# Processor.net
KiCad netlist of a schematic drawn in Altium Designer
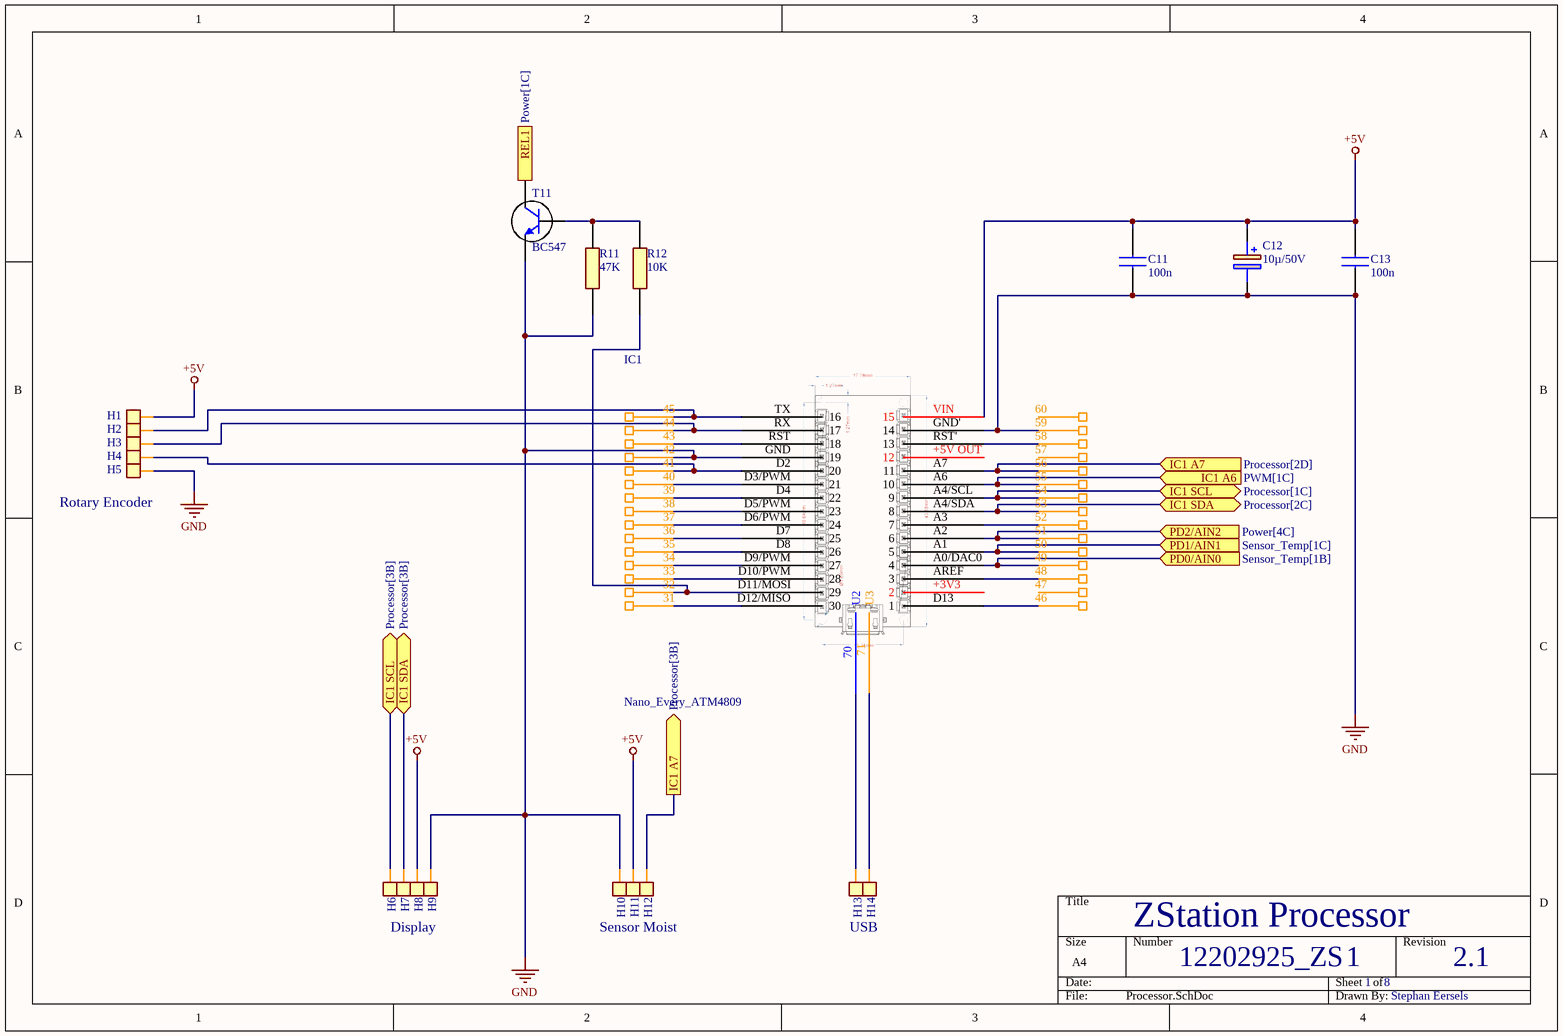
[diagram p0: Processor.SchDoc]

(export (version "E")
  (design (tool "Eeschema 10.0.6"))
  (components
    (comp (ref "C11")
      (value "100n")
      (footprint "RDE5C1H330J0M1H03A")
      (fields
        (field (name "MOUSER PART NUMBER") "80-C315C103K5R-TR")
        (field (name "MANUFACTURER_PART_NUMBER") "C315C103K5R5TA7303")
      )
      (libsource (lib "Master") (part "C315C103K5R5TA7303"))
    )
    (comp (ref "C12")
      (value "10µ/50V")
      (footprint "Master:CAPPRD200W50D525H1250")
      (description "Cap Aluminum Lytic 10uF 50V 10% (5 X 11mm) Radial 2mm 70mA 1000h 105C")
      (fields
        (field (name "MOUSER PART NUMBER") "647-UKL1H100KDDANA")
        (field (name "MANUFACTURER_PART_NUMBER") "UKL1H100KDDANA")
      )
      (libsource (lib "Master") (part "UKL1H100KDDANA"))
    )
    (comp (ref "C13")
      (value "100n")
      (footprint "RDE5C1H330J0M1H03A")
      (fields
        (field (name "MOUSER PART NUMBER") "80-C315C103K5R-TR")
        (field (name "MANUFACTURER_PART_NUMBER") "C315C103K5R5TA7303")
      )
      (libsource (lib "Master") (part "C315C103K5R5TA7303"))
    )
    (comp (ref "H1") (value "HFS") (footprint "Header_F_S") (libsource (lib "") (part "Head_F_S_1")))
    (comp (ref "H2") (value "HFS") (footprint "Header_F_S") (libsource (lib "") (part "Head_F_S_1")))
    (comp (ref "H3") (value "HFS") (footprint "Header_F_S") (libsource (lib "") (part "Head_F_S_1")))
    (comp (ref "H4") (value "HFS") (footprint "Header_F_S") (libsource (lib "") (part "Head_F_S_1")))
    (comp (ref "H5") (value "HFS") (footprint "Header_F_S") (libsource (lib "") (part "Head_F_S_1")))
    (comp (ref "H6") (value "HFS") (footprint "Header_F_S") (libsource (lib "Master") (part "Head_F_S")))
    (comp (ref "H7") (value "HFS") (footprint "Header_F_S") (libsource (lib "Master") (part "Head_F_S")))
    (comp (ref "H8") (value "HFS") (footprint "Header_F_S") (libsource (lib "Master") (part "Head_F_S")))
    (comp (ref "H9") (value "HFS") (footprint "Header_F_S") (libsource (lib "Master") (part "Head_F_S")))
    (comp (ref "H10") (value "HFS") (footprint "Header_F_S") (libsource (lib "Master") (part "Head_F_S")))
    (comp (ref "H11") (value "HFS") (footprint "Header_F_S") (libsource (lib "Master") (part "Head_F_S")))
    (comp (ref "H12") (value "HFS") (footprint "Header_F_S") (libsource (lib "Master") (part "Head_F_S")))
    (comp (ref "H13") (value "HFS") (footprint "Header_F_S") (libsource (lib "Master") (part "Head_F_S")))
    (comp (ref "H14") (value "HFS") (footprint "Header_F_S") (libsource (lib "Master") (part "Head_F_S")))
    (comp (ref "IC1")
      (value "Nano_Every_ATM4809")
      (footprint "Master:Every_Nano_4809")
      (libsource (lib "Master") (part "Nano_Every_ATM4809"))
    )
    (comp (ref "R11")
      (value "47K")
      (footprint "VISHAY_CMF_60")
      (description "Through Hole 1W 10/68 Kohms 1%")
      (fields
        (field (name "MOUSER PART NUMBER") "71-CMF6010K000FKEB")
        (field (name "MANUFACTURER_PART_NUMBER") "CMF6010K000FKEB")
      )
      (libsource (lib "Master") (part "RES_68K_10K"))
    )
    (comp (ref "R12")
      (value "10K")
      (footprint "VISHAY_CMF_60")
      (description "Through Hole 1W 10/68 Kohms 1%")
      (fields
        (field (name "MOUSER PART NUMBER") "71-CMF6010K000FKEB")
        (field (name "MANUFACTURER_PART_NUMBER") "CMF6010K000FKEB")
      )
      (libsource (lib "Master") (part "RES_68K_10K"))
    )
    (comp (ref "T11")
      (value "BC547")
      (footprint "ONSC-TO-92-3-29-11")
      (fields (field (name "MANUFACTURER") "On Semiconductor") (field (name "PARTNUMBER") "BC547C"))
      (libsource (lib "Master") (part "Transistor_NPN"))
    )
  )
  (nets
    (net (code "1") (name "+5V") (class "Default")
      (node (ref "C11") (pin "2") (pinfunction "2_2") (pintype "passive"))
      (node (ref "C12") (pin "1") (pinfunction "+_1") (pintype "passive"))
      (node (ref "C13") (pin "2") (pinfunction "2_2") (pintype "passive"))
      (node (ref "H1") (pin "1") (pinfunction "HF_1") (pintype "passive"))
      (node (ref "H11") (pin "1") (pinfunction "HF_1") (pintype "passive"))
      (node (ref "H8") (pin "1") (pinfunction "HF_1") (pintype "passive"))
      (node (ref "IC1") (pin "VIN") (pinfunction "15_VIN") (pintype "passive"))
    )
    (net (code "2") (name "/IC1 A6") (class "Default")
      (node (ref "IC1") (pin "55") (pinfunction "BIS_55") (pintype "passive"))
      (node (ref "IC1") (pin "A6") (pinfunction "10_A6") (pintype "passive"))
    )
    (net (code "3") (name "/IC1 A7") (class "Default")
      (node (ref "H12") (pin "1") (pinfunction "HF_1") (pintype "passive"))
      (node (ref "IC1") (pin "56") (pinfunction "BIS_56") (pintype "passive"))
      (node (ref "IC1") (pin "A7") (pinfunction "11_A7") (pintype "passive"))
    )
    (net (code "4") (name "/IC1 SCL") (class "Default")
      (node (ref "H6") (pin "1") (pinfunction "HF_1") (pintype "passive"))
      (node (ref "IC1") (pin "54") (pinfunction "BIS_54") (pintype "passive"))
      (node (ref "IC1") (pin "A4/SCL") (pinfunction "9_A4/SCL") (pintype "passive"))
    )
    (net (code "5") (name "/IC1 SDA") (class "Default")
      (node (ref "H7") (pin "1") (pinfunction "HF_1") (pintype "passive"))
      (node (ref "IC1") (pin "53") (pinfunction "BIS_53") (pintype "passive"))
      (node (ref "IC1") (pin "A4/SDA") (pinfunction "8_A4/SDA") (pintype "passive"))
    )
    (net (code "6") (name "/PD0{slash}AIN0") (class "Default")
      (node (ref "IC1") (pin "49") (pinfunction "BIS_49") (pintype "passive"))
      (node (ref "IC1") (pin "A0/DAC0") (pinfunction "4_A0/DAC0") (pintype "passive"))
    )
    (net (code "7") (name "/PD1{slash}AIN1") (class "Default")
      (node (ref "IC1") (pin "50") (pinfunction "BIS_50") (pintype "passive"))
      (node (ref "IC1") (pin "A1") (pinfunction "5_A1") (pintype "passive"))
    )
    (net (code "8") (name "/PD2{slash}AIN2") (class "Default")
      (node (ref "IC1") (pin "51") (pinfunction "BIS_51") (pintype "passive"))
      (node (ref "IC1") (pin "A2") (pinfunction "6_A2") (pintype "passive"))
    )
    (net (code "9") (name "/REL1") (class "Default")
      (node (ref "T11") (pin "1") (pinfunction "C_1") (pintype "passive"))
    )
    (net (code "10") (name "GND") (class "Default")
      (node (ref "C11") (pin "1") (pinfunction "1_1") (pintype "passive"))
      (node (ref "C12") (pin "2") (pinfunction "-_2") (pintype "passive"))
      (node (ref "C13") (pin "1") (pinfunction "1_1") (pintype "passive"))
      (node (ref "H10") (pin "1") (pinfunction "HF_1") (pintype "passive"))
      (node (ref "H5") (pin "1") (pinfunction "HF_1") (pintype "passive"))
      (node (ref "H9") (pin "1") (pinfunction "HF_1") (pintype "passive"))
      (node (ref "IC1") (pin "42") (pinfunction "BIS_42") (pintype "passive"))
      (node (ref "IC1") (pin "59") (pinfunction "BIS_59") (pintype "passive"))
      (node (ref "IC1") (pin "GND") (pinfunction "19_GND") (pintype "passive"))
      (node (ref "IC1") (pin "GND'") (pinfunction "14_GND'") (pintype "passive"))
      (node (ref "R11") (pin "1") (pinfunction "1_1") (pintype "passive"))
      (node (ref "T11") (pin "3") (pinfunction "E_3") (pintype "passive"))
    )
    (net (code "11") (name "Net-(H2-HF)") (class "Default")
      (node (ref "H2") (pin "1") (pinfunction "HF_1") (pintype "passive"))
      (node (ref "IC1") (pin "45") (pinfunction "BIS_45") (pintype "passive"))
      (node (ref "IC1") (pin "TX") (pinfunction "16_TX") (pintype "passive"))
    )
    (net (code "12") (name "Net-(H3-HF)") (class "Default")
      (node (ref "H3") (pin "1") (pinfunction "HF_1") (pintype "passive"))
      (node (ref "IC1") (pin "44") (pinfunction "BIS_44") (pintype "passive"))
      (node (ref "IC1") (pin "RX") (pinfunction "17_RX") (pintype "passive"))
    )
    (net (code "13") (name "Net-(H4-HF)") (class "Default")
      (node (ref "H4") (pin "1") (pinfunction "HF_1") (pintype "passive"))
      (node (ref "IC1") (pin "41") (pinfunction "BIS_41") (pintype "passive"))
      (node (ref "IC1") (pin "D2") (pinfunction "20_D2") (pintype "passive"))
    )
    (net (code "14") (name "Net-(H13-HF)") (class "Default")
      (node (ref "H13") (pin "1") (pinfunction "HF_1") (pintype "passive"))
      (node (ref "IC1") (pin "70") (pinfunction "U2_70") (pintype "passive"))
    )
    (net (code "15") (name "Net-(H14-HF)") (class "Default")
      (node (ref "H14") (pin "1") (pinfunction "HF_1") (pintype "passive"))
      (node (ref "IC1") (pin "71") (pinfunction "U3_71") (pintype "passive"))
    )
    (net (code "16") (name "Net-(IC1-1)") (class "Default")
      (node (ref "IC1") (pin "46") (pinfunction "BIS_46") (pintype "passive"))
      (node (ref "IC1") (pin "D13") (pinfunction "1_D13") (pintype "passive"))
    )
    (net (code "17") (name "Net-(IC1-3)") (class "Default")
      (node (ref "IC1") (pin "48") (pinfunction "BIS_48") (pintype "passive"))
      (node (ref "IC1") (pin "AREF") (pinfunction "3_AREF") (pintype "passive"))
    )
    (net (code "18") (name "Net-(IC1-7)") (class "Default")
      (node (ref "IC1") (pin "52") (pinfunction "BIS_52") (pintype "passive"))
      (node (ref "IC1") (pin "A3") (pinfunction "7_A3") (pintype "passive"))
    )
    (net (code "19") (name "Net-(IC1-13)") (class "Default")
      (node (ref "IC1") (pin "58") (pinfunction "BIS_58") (pintype "passive"))
      (node (ref "IC1") (pin "RST'") (pinfunction "13_RST'") (pintype "passive"))
    )
    (net (code "20") (name "Net-(IC1-18)") (class "Default")
      (node (ref "IC1") (pin "43") (pinfunction "BIS_43") (pintype "passive"))
      (node (ref "IC1") (pin "RST") (pinfunction "18_RST") (pintype "passive"))
    )
    (net (code "21") (name "Net-(IC1-21)") (class "Default")
      (node (ref "IC1") (pin "40") (pinfunction "BIS_40") (pintype "passive"))
      (node (ref "IC1") (pin "D3/PWM") (pinfunction "21_D3/PWM") (pintype "passive"))
    )
    (net (code "22") (name "Net-(IC1-22)") (class "Default")
      (node (ref "IC1") (pin "39") (pinfunction "BIS_39") (pintype "passive"))
      (node (ref "IC1") (pin "D4") (pinfunction "22_D4") (pintype "passive"))
    )
    (net (code "23") (name "Net-(IC1-23)") (class "Default")
      (node (ref "IC1") (pin "38") (pinfunction "BIS_38") (pintype "passive"))
      (node (ref "IC1") (pin "D5/PWM") (pinfunction "23_D5/PWM") (pintype "passive"))
    )
    (net (code "24") (name "Net-(IC1-24)") (class "Default")
      (node (ref "IC1") (pin "37") (pinfunction "BIS_37") (pintype "passive"))
      (node (ref "IC1") (pin "D6/PWM") (pinfunction "24_D6/PWM") (pintype "passive"))
    )
    (net (code "25") (name "Net-(IC1-25)") (class "Default")
      (node (ref "IC1") (pin "36") (pinfunction "BIS_36") (pintype "passive"))
      (node (ref "IC1") (pin "D7") (pinfunction "25_D7") (pintype "passive"))
    )
    (net (code "26") (name "Net-(IC1-26)") (class "Default")
      (node (ref "IC1") (pin "35") (pinfunction "BIS_35") (pintype "passive"))
      (node (ref "IC1") (pin "D8") (pinfunction "26_D8") (pintype "passive"))
    )
    (net (code "27") (name "Net-(IC1-27)") (class "Default")
      (node (ref "IC1") (pin "34") (pinfunction "BIS_34") (pintype "passive"))
      (node (ref "IC1") (pin "D9/PWM") (pinfunction "27_D9/PWM") (pintype "passive"))
    )
    (net (code "28") (name "Net-(IC1-28)") (class "Default")
      (node (ref "IC1") (pin "33") (pinfunction "BIS_33") (pintype "passive"))
      (node (ref "IC1") (pin "D10/PWM") (pinfunction "28_D10/PWM") (pintype "passive"))
    )
    (net (code "29") (name "Net-(IC1-29)") (class "Default")
      (node (ref "IC1") (pin "32") (pinfunction "BIS_32") (pintype "passive"))
      (node (ref "IC1") (pin "D11/MOSI") (pinfunction "29_D11/MOSI") (pintype "passive"))
      (node (ref "R12") (pin "1") (pinfunction "1_1") (pintype "passive"))
    )
    (net (code "30") (name "Net-(IC1-30)") (class "Default")
      (node (ref "IC1") (pin "31") (pinfunction "BIS_31") (pintype "passive"))
      (node (ref "IC1") (pin "D12/MISO") (pinfunction "30_D12/MISO") (pintype "passive"))
    )
    (net (code "31") (name "Net-(T11-B)") (class "Default")
      (node (ref "R11") (pin "2") (pinfunction "2_2") (pintype "passive"))
      (node (ref "R12") (pin "2") (pinfunction "2_2") (pintype "passive"))
      (node (ref "T11") (pin "2") (pinfunction "B_2") (pintype "passive"))
    )
    (net (code "32") (name "unconnected-(IC1-2-Pad+3V3)") (class "Default")
      (node (ref "IC1") (pin "+3V3") (pinfunction "2_+3V3") (pintype "passive"))
    )
    (net (code "33") (name "unconnected-(IC1-12-Pad+5V_OUT)") (class "Default")
      (node (ref "IC1") (pin "+5V_OUT") (pinfunction "12_+5V_OUT") (pintype "passive"))
    )
    (net (code "34") (name "unconnected-(IC1-BIS-Pad47)") (class "Default")
      (node (ref "IC1") (pin "47") (pinfunction "BIS_47") (pintype "passive"))
    )
    (net (code "35") (name "unconnected-(IC1-BIS-Pad57)") (class "Default")
      (node (ref "IC1") (pin "57") (pinfunction "BIS_57") (pintype "passive"))
    )
    (net (code "36") (name "unconnected-(IC1-BIS-Pad60)") (class "Default")
      (node (ref "IC1") (pin "60") (pinfunction "BIS_60") (pintype "passive"))
    )
  )
)
